# PGA.net
KiCad netlist of a schematic drawn in Altium Designer
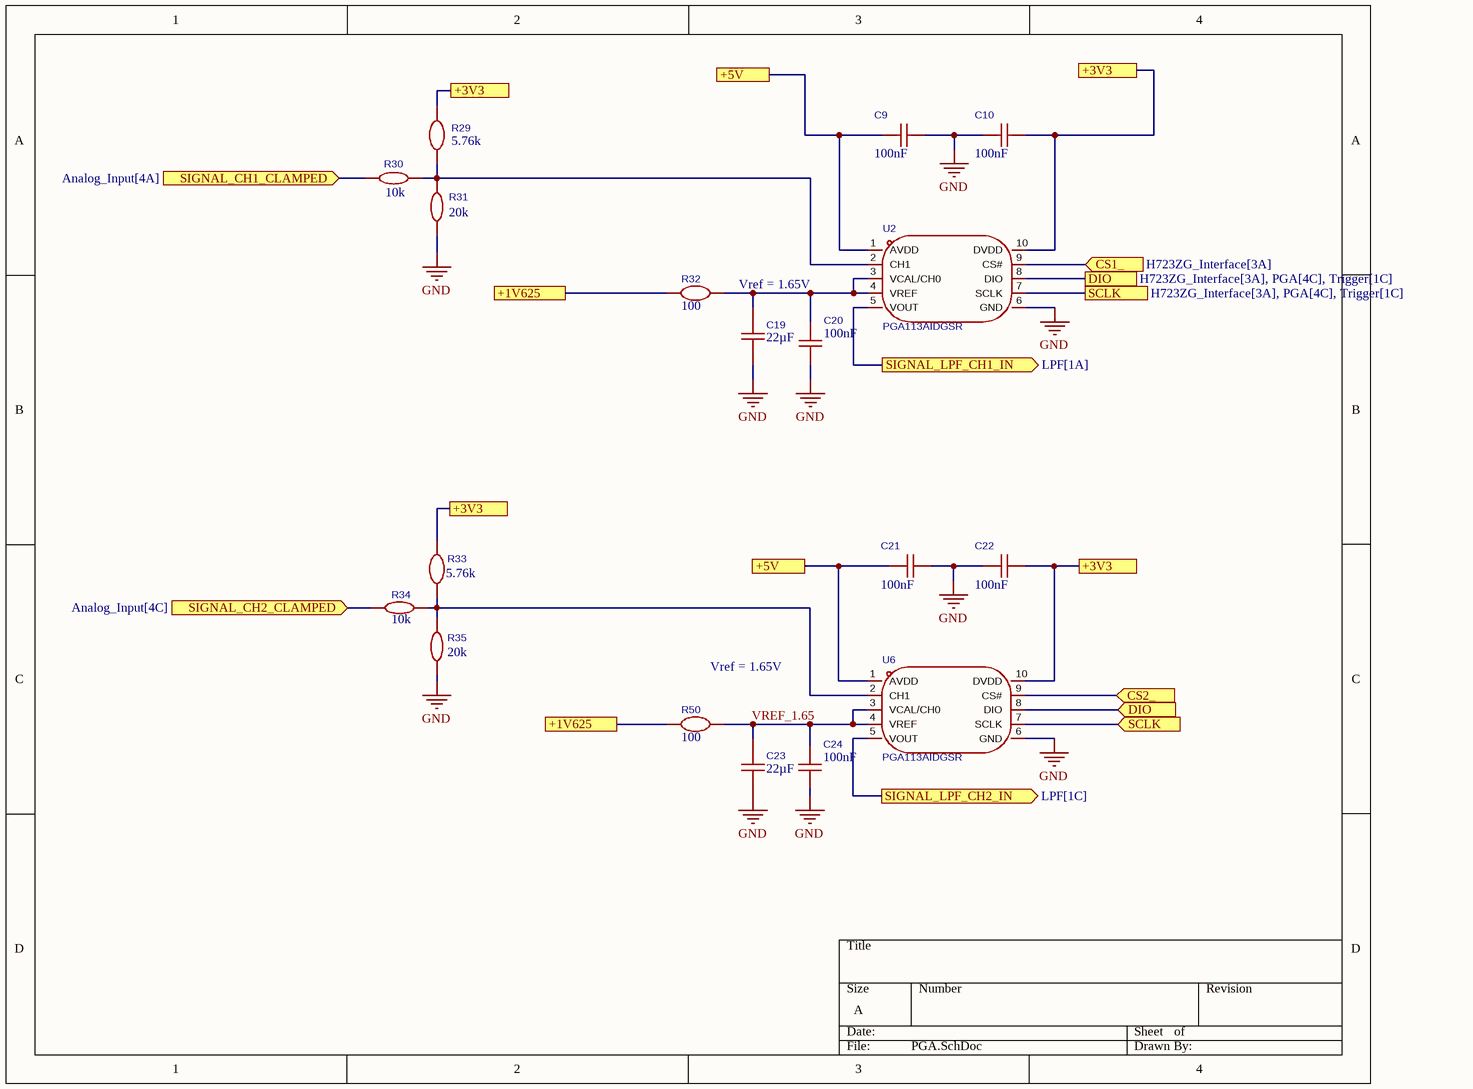
[diagram p0: PGA.SchDoc]

(export (version "E")
  (design (tool "Eeschema 10.0.6"))
  (components
    (comp (ref "C9")
      (value "100nF")
      (footprint "C0805")
      (description "Capacitance:100nF Tolerance:±5% Tolerance:±5% Voltage Rating:50V Temperature Coefficient:X7R")
      (fields (field (name "MANUFACTURER") "YAGEO(国巨)") (field (name "TOLERANCE") "5%"))
      (libsource (lib "zhiming xue") (part "0805CG6R0C500NT_C67560"))
    )
    (comp (ref "C10")
      (value "100nF")
      (footprint "C0805")
      (description "Capacitance:100nF Tolerance:±5% Tolerance:±5% Voltage Rating:50V Temperature Coefficient:X7R")
      (fields (field (name "MANUFACTURER") "YAGEO(国巨)") (field (name "TOLERANCE") "5%"))
      (libsource (lib "zhiming xue") (part "0805CG6R0C500NT_C67560"))
    )
    (comp (ref "C19")
      (value "22µF")
      (footprint "C0805")
      (description "Capacitance:22uF Tolerance:±10% Tolerance:±10% Voltage Rating:10V Temperature Coefficient:X5R")
      (fields (field (name "MANUFACTURER") "CCTC(三环)") (field (name "TOLERANCE") "10%"))
      (libsource (lib "zhiming xue") (part "TCC0805X5R226K100FT"))
    )
    (comp (ref "C20")
      (value "100nF")
      (footprint "C0805")
      (description "Capacitance:100nF Tolerance:±5% Tolerance:±5% Voltage Rating:50V Temperature Coefficient:X7R")
      (fields (field (name "MANUFACTURER") "YAGEO(国巨)") (field (name "TOLERANCE") "5%"))
      (libsource (lib "zhiming xue") (part "0805CG6R0C500NT_C67560"))
    )
    (comp (ref "C21")
      (value "100nF")
      (footprint "C0805")
      (description "Capacitance:100nF Tolerance:±5% Tolerance:±5% Voltage Rating:50V Temperature Coefficient:X7R")
      (fields (field (name "MANUFACTURER") "YAGEO(国巨)") (field (name "TOLERANCE") "5%"))
      (libsource (lib "zhiming xue") (part "0805CG6R0C500NT_C67560"))
    )
    (comp (ref "C22")
      (value "100nF")
      (footprint "C0805")
      (description "Capacitance:100nF Tolerance:±5% Tolerance:±5% Voltage Rating:50V Temperature Coefficient:X7R")
      (fields (field (name "MANUFACTURER") "YAGEO(国巨)") (field (name "TOLERANCE") "5%"))
      (libsource (lib "zhiming xue") (part "0805CG6R0C500NT_C67560"))
    )
    (comp (ref "C23")
      (value "22µF")
      (footprint "C0805")
      (description "Capacitance:22uF Tolerance:±10% Tolerance:±10% Voltage Rating:10V Temperature Coefficient:X5R")
      (fields (field (name "MANUFACTURER") "CCTC(三环)") (field (name "TOLERANCE") "10%"))
      (libsource (lib "zhiming xue") (part "TCC0805X5R226K100FT"))
    )
    (comp (ref "C24")
      (value "100nF")
      (footprint "C0805")
      (description "Capacitance:100nF Tolerance:±5% Tolerance:±5% Voltage Rating:50V Temperature Coefficient:X7R")
      (fields (field (name "MANUFACTURER") "YAGEO(国巨)") (field (name "TOLERANCE") "5%"))
      (libsource (lib "zhiming xue") (part "0805CG6R0C500NT_C67560"))
    )
    (comp (ref "R29")
      (value "5.76k")
      (footprint "R0805")
      (fields
        (field (name "MANUFACTURER") "FOJAN(富捷)")
        (field (name "TOLERANCE") "1%")
        (field (name "MANUFACTURER PART NUMBER") "FRC0805F5761TS")
      )
      (libsource (lib "zhiming xue") (part "RT0805BRD0710K1L"))
    )
    (comp (ref "R30")
      (value "10k")
      (footprint "R0805")
      (fields
        (field (name "MANUFACTURER") "UNI-ROYAL(厚声)")
        (field (name "TOLERANCE") "1%")
        (field (name "MANUFACTURER PART NUMBER") "0805W8F1002T5E")
      )
      (libsource (lib "zhiming xue") (part "0805W8F0000T5E_C17477"))
    )
    (comp (ref "R31")
      (value "20k")
      (footprint "R0805")
      (fields
        (field (name "MANUFACTURER") "UNI-ROYAL(厚声)")
        (field (name "TOLERANCE") "1%")
        (field (name "MANUFACTURER PART NUMBER") "0805W8F2002T5E")
      )
      (libsource (lib "zhiming xue") (part "0805W8F0000T5E_C17477"))
    )
    (comp (ref "R32")
      (value "100")
      (footprint "R0805")
      (fields
        (field (name "MANUFACTURER") "FOJAN(富捷)")
        (field (name "TOLERANCE") "1%")
        (field (name "MANUFACTURER PART NUMBER") "FRC0805F1000TS")
      )
      (libsource (lib "zhiming xue") (part "RT0805BRD0710K1L"))
    )
    (comp (ref "R33")
      (value "5.76k")
      (footprint "R0805")
      (fields
        (field (name "MANUFACTURER") "FOJAN(富捷)")
        (field (name "TOLERANCE") "1%")
        (field (name "MANUFACTURER PART NUMBER") "FRC0805F5761TS")
      )
      (libsource (lib "zhiming xue") (part "RT0805BRD0710K1L"))
    )
    (comp (ref "R34")
      (value "10k")
      (footprint "R0805")
      (fields
        (field (name "MANUFACTURER") "UNI-ROYAL(厚声)")
        (field (name "TOLERANCE") "1%")
        (field (name "MANUFACTURER PART NUMBER") "0805W8F1002T5E")
      )
      (libsource (lib "zhiming xue") (part "0805W8F0000T5E_C17477"))
    )
    (comp (ref "R35")
      (value "20k")
      (footprint "R0805")
      (fields
        (field (name "MANUFACTURER") "UNI-ROYAL(厚声)")
        (field (name "TOLERANCE") "1%")
        (field (name "MANUFACTURER PART NUMBER") "0805W8F2002T5E")
      )
      (libsource (lib "zhiming xue") (part "0805W8F0000T5E_C17477"))
    )
    (comp (ref "R50")
      (value "100")
      (footprint "R0805")
      (fields
        (field (name "MANUFACTURER") "FOJAN(富捷)")
        (field (name "TOLERANCE") "1%")
        (field (name "MANUFACTURER PART NUMBER") "FRC0805F1000TS")
      )
      (libsource (lib "zhiming xue") (part "RT0805BRD0710K1L"))
    )
    (comp (ref "U2")
      (value "PGA113AIDGSR")
      (footprint "VSSOP-10_L3.0-W3.0-P0.50-LS4.9-BL")
      (fields (field (name "MANUFACTURER") "TI(德州仪器)"))
      (libsource (lib "zhiming xue") (part "PGA113AIDGSR"))
    )
    (comp (ref "U6")
      (value "PGA113AIDGSR")
      (footprint "VSSOP-10_L3.0-W3.0-P0.50-LS4.9-BL")
      (fields (field (name "MANUFACTURER") "TI(德州仪器)"))
      (libsource (lib "zhiming xue") (part "PGA113AIDGSR"))
    )
  )
  (nets
    (net (code "1") (name "/+1V625") (class "Default")
      (node (ref "R32") (pin "1") (pinfunction "1_1") (pintype "passive"))
      (node (ref "R50") (pin "1") (pinfunction "1_1") (pintype "passive"))
    )
    (net (code "2") (name "/+3V3") (class "Default")
      (node (ref "C10") (pin "1") (pinfunction "1_1") (pintype "passive"))
      (node (ref "C22") (pin "1") (pinfunction "1_1") (pintype "passive"))
      (node (ref "R29") (pin "1") (pinfunction "1_1") (pintype "passive"))
      (node (ref "R33") (pin "1") (pinfunction "1_1") (pintype "passive"))
      (node (ref "U2") (pin "10") (pinfunction "DVDD_10") (pintype "passive"))
      (node (ref "U6") (pin "10") (pinfunction "DVDD_10") (pintype "passive"))
    )
    (net (code "3") (name "/+5V") (class "Default")
      (node (ref "C21") (pin "2") (pinfunction "2_2") (pintype "passive"))
      (node (ref "C9") (pin "2") (pinfunction "2_2") (pintype "passive"))
      (node (ref "U2") (pin "1") (pinfunction "AVDD_1") (pintype "passive"))
      (node (ref "U6") (pin "1") (pinfunction "AVDD_1") (pintype "passive"))
    )
    (net (code "4") (name "/CS1_") (class "Default")
      (node (ref "U2") (pin "9") (pinfunction "CS#_9") (pintype "passive"))
    )
    (net (code "5") (name "/CS2_") (class "Default")
      (node (ref "U6") (pin "9") (pinfunction "CS#_9") (pintype "passive"))
    )
    (net (code "6") (name "/DIO") (class "Default")
      (node (ref "U2") (pin "8") (pinfunction "DIO_8") (pintype "passive"))
      (node (ref "U6") (pin "8") (pinfunction "DIO_8") (pintype "passive"))
    )
    (net (code "7") (name "/SCLK") (class "Default")
      (node (ref "U2") (pin "7") (pinfunction "SCLK_7") (pintype "passive"))
      (node (ref "U6") (pin "7") (pinfunction "SCLK_7") (pintype "passive"))
    )
    (net (code "8") (name "/SIGNAL_CH1_CLAMPED") (class "Default")
      (node (ref "R30") (pin "2") (pinfunction "2_2") (pintype "passive"))
    )
    (net (code "9") (name "/SIGNAL_CH2_CLAMPED") (class "Default")
      (node (ref "R34") (pin "2") (pinfunction "2_2") (pintype "passive"))
    )
    (net (code "10") (name "/SIGNAL_LPF_CH1_IN") (class "Default")
      (node (ref "U2") (pin "5") (pinfunction "VOUT_5") (pintype "passive"))
    )
    (net (code "11") (name "/SIGNAL_LPF_CH2_IN") (class "Default")
      (node (ref "U6") (pin "5") (pinfunction "VOUT_5") (pintype "passive"))
    )
    (net (code "12") (name "/VREF_1.65") (class "Default")
      (node (ref "C23") (pin "1") (pinfunction "1_1") (pintype "passive"))
      (node (ref "C24") (pin "2") (pinfunction "2_2") (pintype "passive"))
      (node (ref "R50") (pin "2") (pinfunction "2_2") (pintype "passive"))
      (node (ref "U6") (pin "3") (pinfunction "VCAL/CH0_3") (pintype "passive"))
      (node (ref "U6") (pin "4") (pinfunction "VREF_4") (pintype "passive"))
    )
    (net (code "13") (name "GND") (class "Default")
      (node (ref "C10") (pin "2") (pinfunction "2_2") (pintype "passive"))
      (node (ref "C19") (pin "2") (pinfunction "2_2") (pintype "passive"))
      (node (ref "C20") (pin "1") (pinfunction "1_1") (pintype "passive"))
      (node (ref "C21") (pin "1") (pinfunction "1_1") (pintype "passive"))
      (node (ref "C22") (pin "2") (pinfunction "2_2") (pintype "passive"))
      (node (ref "C23") (pin "2") (pinfunction "2_2") (pintype "passive"))
      (node (ref "C24") (pin "1") (pinfunction "1_1") (pintype "passive"))
      (node (ref "C9") (pin "1") (pinfunction "1_1") (pintype "passive"))
      (node (ref "R31") (pin "2") (pinfunction "2_2") (pintype "passive"))
      (node (ref "R35") (pin "2") (pinfunction "2_2") (pintype "passive"))
      (node (ref "U2") (pin "6") (pinfunction "GND_6") (pintype "passive"))
      (node (ref "U6") (pin "6") (pinfunction "GND_6") (pintype "passive"))
    )
    (net (code "14") (name "Net-(U2-CH1)") (class "Default")
      (node (ref "R29") (pin "2") (pinfunction "2_2") (pintype "passive"))
      (node (ref "R30") (pin "1") (pinfunction "1_1") (pintype "passive"))
      (node (ref "R31") (pin "1") (pinfunction "1_1") (pintype "passive"))
      (node (ref "U2") (pin "2") (pinfunction "CH1_2") (pintype "passive"))
    )
    (net (code "15") (name "Net-(U2-VCAL{slash}CH0)") (class "Default")
      (node (ref "C19") (pin "1") (pinfunction "1_1") (pintype "passive"))
      (node (ref "C20") (pin "2") (pinfunction "2_2") (pintype "passive"))
      (node (ref "R32") (pin "2") (pinfunction "2_2") (pintype "passive"))
      (node (ref "U2") (pin "3") (pinfunction "VCAL/CH0_3") (pintype "passive"))
      (node (ref "U2") (pin "4") (pinfunction "VREF_4") (pintype "passive"))
    )
    (net (code "16") (name "Net-(U6-CH1)") (class "Default")
      (node (ref "R33") (pin "2") (pinfunction "2_2") (pintype "passive"))
      (node (ref "R34") (pin "1") (pinfunction "1_1") (pintype "passive"))
      (node (ref "R35") (pin "1") (pinfunction "1_1") (pintype "passive"))
      (node (ref "U6") (pin "2") (pinfunction "CH1_2") (pintype "passive"))
    )
  )
)
